# vu3.net
KiCad netlist of a schematic drawn in EAGLE
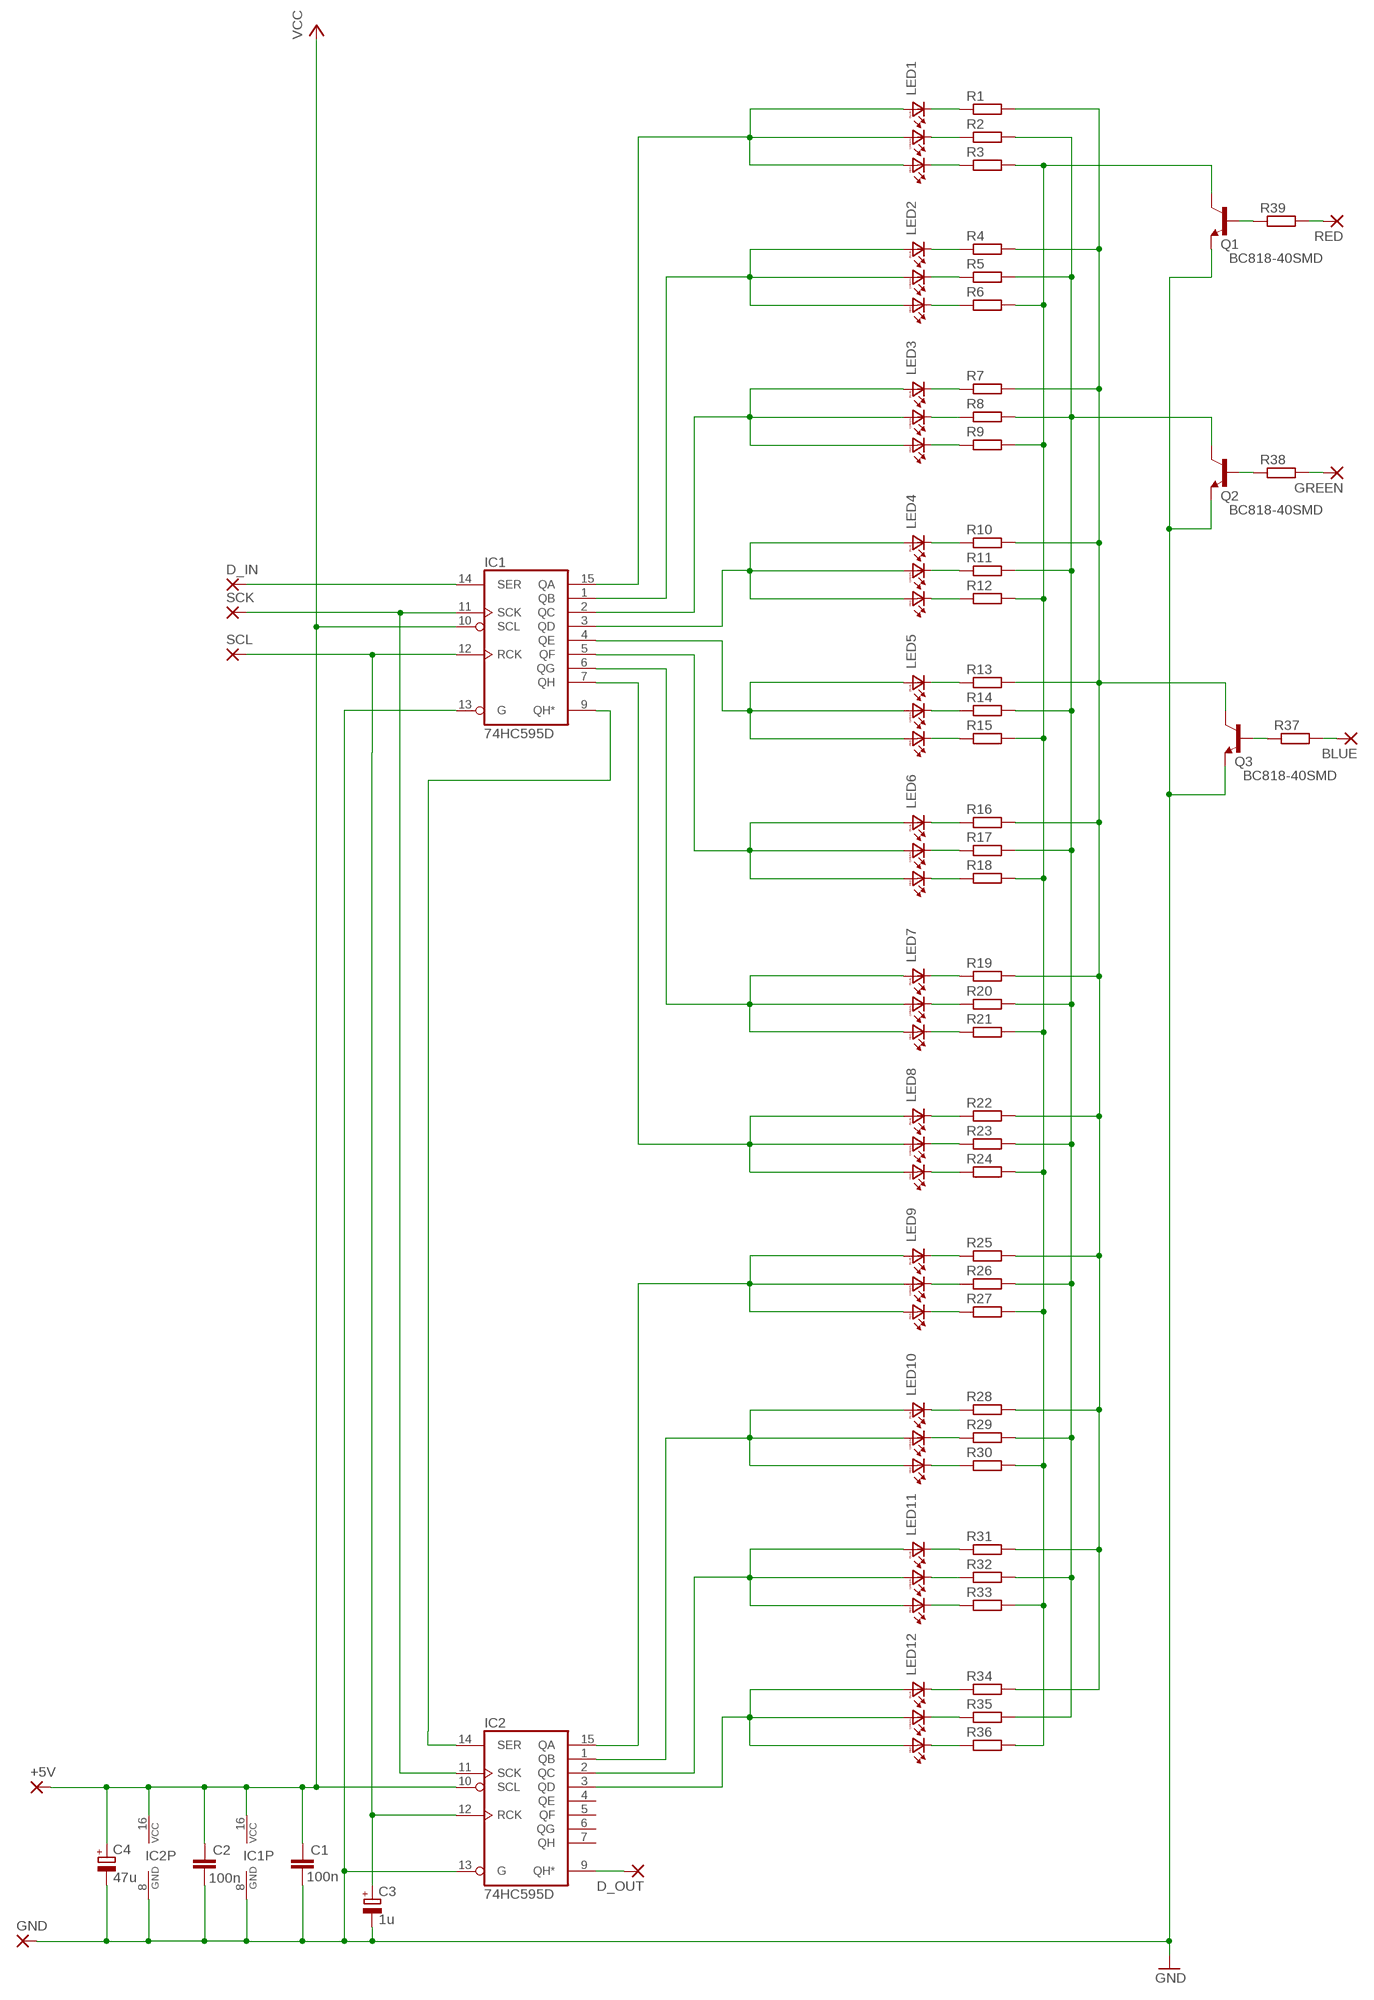
[diagram p0: schematic, sheet 1]

(export (version "E")
  (design (tool "Eeschema 10.0.6"))
  (components
    (comp (ref "+5V")
      (value "2,54/0,8")
      (footprint "eagle-import:2,54_0,8")
      (libsource (lib "eagle-import") (part "2,54/0,8"))
    )
    (comp (ref "BLUE")
      (value "2,54/0,8")
      (footprint "eagle-import:2,54_0,8")
      (libsource (lib "eagle-import") (part "2,54/0,8"))
    )
    (comp (ref "C1")
      (value "100n")
      (footprint "eagle-import:C1206")
      (libsource (lib "eagle-import") (part "C-EUC1206"))
    )
    (comp (ref "C2")
      (value "100n")
      (footprint "eagle-import:C1206")
      (libsource (lib "eagle-import") (part "C-EUC1206"))
    )
    (comp (ref "C3")
      (value "1u")
      (footprint "eagle-import:E5-5-L-12SMD")
      (libsource (lib "eagle-import") (part "CPOL-EUE5-5-L-12SMD"))
    )
    (comp (ref "C4")
      (value "47u")
      (footprint "eagle-import:E2,5-5-L-12SMD")
      (libsource (lib "eagle-import") (part "CPOL-EUE2.5-5-L-12-SMD"))
    )
    (comp (ref "D_IN")
      (value "2,54/0,8")
      (footprint "eagle-import:2,54_0,8")
      (libsource (lib "eagle-import") (part "2,54/0,8"))
    )
    (comp (ref "D_OUT")
      (value "2,54/0,8")
      (footprint "eagle-import:2,54_0,8")
      (libsource (lib "eagle-import") (part "2,54/0,8"))
    )
    (comp (ref "GND")
      (value "2,54/0,8")
      (footprint "eagle-import:2,54_0,8")
      (libsource (lib "eagle-import") (part "2,54/0,8"))
    )
    (comp (ref "GREEN")
      (value "2,54/0,8")
      (footprint "eagle-import:2,54_0,8")
      (libsource (lib "eagle-import") (part "2,54/0,8"))
    )
    (comp (ref "IC1")
      (value "74HC595D")
      (footprint "eagle-import:SO16")
      (libsource (lib "eagle-import") (part "74595DHC"))
    )
    (comp (ref "IC2")
      (value "74HC595D")
      (footprint "eagle-import:SO16")
      (libsource (lib "eagle-import") (part "74595DHC"))
    )
    (comp (ref "LED1")
      (value "LED_RGB_PLCC6")
      (footprint "eagle-import:PLCC6")
      (libsource (lib "eagle-import") (part "LED_RGB_PLCC6"))
    )
    (comp (ref "LED2")
      (value "LED_RGB_PLCC6")
      (footprint "eagle-import:PLCC6")
      (libsource (lib "eagle-import") (part "LED_RGB_PLCC6"))
    )
    (comp (ref "LED3")
      (value "LED_RGB_PLCC6")
      (footprint "eagle-import:PLCC6")
      (libsource (lib "eagle-import") (part "LED_RGB_PLCC6"))
    )
    (comp (ref "LED4")
      (value "LED_RGB_PLCC6")
      (footprint "eagle-import:PLCC6")
      (libsource (lib "eagle-import") (part "LED_RGB_PLCC6"))
    )
    (comp (ref "LED5")
      (value "LED_RGB_PLCC6")
      (footprint "eagle-import:PLCC6")
      (libsource (lib "eagle-import") (part "LED_RGB_PLCC6"))
    )
    (comp (ref "LED6")
      (value "LED_RGB_PLCC6")
      (footprint "eagle-import:PLCC6")
      (libsource (lib "eagle-import") (part "LED_RGB_PLCC6"))
    )
    (comp (ref "LED7")
      (value "LED_RGB_PLCC6")
      (footprint "eagle-import:PLCC6")
      (libsource (lib "eagle-import") (part "LED_RGB_PLCC6"))
    )
    (comp (ref "LED8")
      (value "LED_RGB_PLCC6")
      (footprint "eagle-import:PLCC6")
      (libsource (lib "eagle-import") (part "LED_RGB_PLCC6"))
    )
    (comp (ref "LED9")
      (value "LED_RGB_PLCC6")
      (footprint "eagle-import:PLCC6")
      (libsource (lib "eagle-import") (part "LED_RGB_PLCC6"))
    )
    (comp (ref "LED10")
      (value "LED_RGB_PLCC6")
      (footprint "eagle-import:PLCC6")
      (libsource (lib "eagle-import") (part "LED_RGB_PLCC6"))
    )
    (comp (ref "LED11")
      (value "LED_RGB_PLCC6")
      (footprint "eagle-import:PLCC6")
      (libsource (lib "eagle-import") (part "LED_RGB_PLCC6"))
    )
    (comp (ref "LED12")
      (value "LED_RGB_PLCC6")
      (footprint "eagle-import:PLCC6")
      (libsource (lib "eagle-import") (part "LED_RGB_PLCC6"))
    )
    (comp (ref "Q1")
      (value "BC818-40SMD")
      (footprint "eagle-import:SOT23-BEC")
      (libsource (lib "eagle-import") (part "BC818SMD-40"))
    )
    (comp (ref "Q2")
      (value "BC818-40SMD")
      (footprint "eagle-import:SOT23-BEC")
      (libsource (lib "eagle-import") (part "BC818SMD-40"))
    )
    (comp (ref "Q3")
      (value "BC818-40SMD")
      (footprint "eagle-import:SOT23-BEC")
      (libsource (lib "eagle-import") (part "BC818SMD-40"))
    )
    (comp (ref "R1")
      (value "R-EU_R1206")
      (footprint "eagle-import:R1206")
      (libsource (lib "eagle-import") (part "R-EU_R1206"))
    )
    (comp (ref "R2")
      (value "R-EU_R1206")
      (footprint "eagle-import:R1206")
      (libsource (lib "eagle-import") (part "R-EU_R1206"))
    )
    (comp (ref "R3")
      (value "R-EU_R1206")
      (footprint "eagle-import:R1206")
      (libsource (lib "eagle-import") (part "R-EU_R1206"))
    )
    (comp (ref "R4")
      (value "R-EU_R1206")
      (footprint "eagle-import:R1206")
      (libsource (lib "eagle-import") (part "R-EU_R1206"))
    )
    (comp (ref "R5")
      (value "R-EU_R1206")
      (footprint "eagle-import:R1206")
      (libsource (lib "eagle-import") (part "R-EU_R1206"))
    )
    (comp (ref "R6")
      (value "R-EU_R1206")
      (footprint "eagle-import:R1206")
      (libsource (lib "eagle-import") (part "R-EU_R1206"))
    )
    (comp (ref "R7")
      (value "R-EU_R1206")
      (footprint "eagle-import:R1206")
      (libsource (lib "eagle-import") (part "R-EU_R1206"))
    )
    (comp (ref "R8")
      (value "R-EU_R1206")
      (footprint "eagle-import:R1206")
      (libsource (lib "eagle-import") (part "R-EU_R1206"))
    )
    (comp (ref "R9")
      (value "R-EU_R1206")
      (footprint "eagle-import:R1206")
      (libsource (lib "eagle-import") (part "R-EU_R1206"))
    )
    (comp (ref "R10")
      (value "R-EU_R1206")
      (footprint "eagle-import:R1206")
      (libsource (lib "eagle-import") (part "R-EU_R1206"))
    )
    (comp (ref "R11")
      (value "R-EU_R1206")
      (footprint "eagle-import:R1206")
      (libsource (lib "eagle-import") (part "R-EU_R1206"))
    )
    (comp (ref "R12")
      (value "R-EU_R1206")
      (footprint "eagle-import:R1206")
      (libsource (lib "eagle-import") (part "R-EU_R1206"))
    )
    (comp (ref "R13")
      (value "R-EU_R1206")
      (footprint "eagle-import:R1206")
      (libsource (lib "eagle-import") (part "R-EU_R1206"))
    )
    (comp (ref "R14")
      (value "R-EU_R1206")
      (footprint "eagle-import:R1206")
      (libsource (lib "eagle-import") (part "R-EU_R1206"))
    )
    (comp (ref "R15")
      (value "R-EU_R1206")
      (footprint "eagle-import:R1206")
      (libsource (lib "eagle-import") (part "R-EU_R1206"))
    )
    (comp (ref "R16")
      (value "R-EU_R1206")
      (footprint "eagle-import:R1206")
      (libsource (lib "eagle-import") (part "R-EU_R1206"))
    )
    (comp (ref "R17")
      (value "R-EU_R1206")
      (footprint "eagle-import:R1206")
      (libsource (lib "eagle-import") (part "R-EU_R1206"))
    )
    (comp (ref "R18")
      (value "R-EU_R1206")
      (footprint "eagle-import:R1206")
      (libsource (lib "eagle-import") (part "R-EU_R1206"))
    )
    (comp (ref "R19")
      (value "R-EU_R1206")
      (footprint "eagle-import:R1206")
      (libsource (lib "eagle-import") (part "R-EU_R1206"))
    )
    (comp (ref "R20")
      (value "R-EU_R1206")
      (footprint "eagle-import:R1206")
      (libsource (lib "eagle-import") (part "R-EU_R1206"))
    )
    (comp (ref "R21")
      (value "R-EU_R1206")
      (footprint "eagle-import:R1206")
      (libsource (lib "eagle-import") (part "R-EU_R1206"))
    )
    (comp (ref "R22")
      (value "R-EU_R1206")
      (footprint "eagle-import:R1206")
      (libsource (lib "eagle-import") (part "R-EU_R1206"))
    )
    (comp (ref "R23")
      (value "R-EU_R1206")
      (footprint "eagle-import:R1206")
      (libsource (lib "eagle-import") (part "R-EU_R1206"))
    )
    (comp (ref "R24")
      (value "R-EU_R1206")
      (footprint "eagle-import:R1206")
      (libsource (lib "eagle-import") (part "R-EU_R1206"))
    )
    (comp (ref "R25")
      (value "R-EU_R1206")
      (footprint "eagle-import:R1206")
      (libsource (lib "eagle-import") (part "R-EU_R1206"))
    )
    (comp (ref "R26")
      (value "R-EU_R1206")
      (footprint "eagle-import:R1206")
      (libsource (lib "eagle-import") (part "R-EU_R1206"))
    )
    (comp (ref "R27")
      (value "R-EU_R1206")
      (footprint "eagle-import:R1206")
      (libsource (lib "eagle-import") (part "R-EU_R1206"))
    )
    (comp (ref "R28")
      (value "R-EU_R1206")
      (footprint "eagle-import:R1206")
      (libsource (lib "eagle-import") (part "R-EU_R1206"))
    )
    (comp (ref "R29")
      (value "R-EU_R1206")
      (footprint "eagle-import:R1206")
      (libsource (lib "eagle-import") (part "R-EU_R1206"))
    )
    (comp (ref "R30")
      (value "R-EU_R1206")
      (footprint "eagle-import:R1206")
      (libsource (lib "eagle-import") (part "R-EU_R1206"))
    )
    (comp (ref "R31")
      (value "R-EU_R1206")
      (footprint "eagle-import:R1206")
      (libsource (lib "eagle-import") (part "R-EU_R1206"))
    )
    (comp (ref "R32")
      (value "R-EU_R1206")
      (footprint "eagle-import:R1206")
      (libsource (lib "eagle-import") (part "R-EU_R1206"))
    )
    (comp (ref "R33")
      (value "R-EU_R1206")
      (footprint "eagle-import:R1206")
      (libsource (lib "eagle-import") (part "R-EU_R1206"))
    )
    (comp (ref "R34")
      (value "R-EU_R1206")
      (footprint "eagle-import:R1206")
      (libsource (lib "eagle-import") (part "R-EU_R1206"))
    )
    (comp (ref "R35")
      (value "R-EU_R1206")
      (footprint "eagle-import:R1206")
      (libsource (lib "eagle-import") (part "R-EU_R1206"))
    )
    (comp (ref "R36")
      (value "R-EU_R1206")
      (footprint "eagle-import:R1206")
      (libsource (lib "eagle-import") (part "R-EU_R1206"))
    )
    (comp (ref "R37")
      (value "R-EU_R1206")
      (footprint "eagle-import:R1206")
      (libsource (lib "eagle-import") (part "R-EU_R1206"))
    )
    (comp (ref "R38")
      (value "R-EU_R1206")
      (footprint "eagle-import:R1206")
      (libsource (lib "eagle-import") (part "R-EU_R1206"))
    )
    (comp (ref "R39")
      (value "R-EU_R1206")
      (footprint "eagle-import:R1206")
      (libsource (lib "eagle-import") (part "R-EU_R1206"))
    )
    (comp (ref "RED")
      (value "2,54/0,8")
      (footprint "eagle-import:2,54_0,8")
      (libsource (lib "eagle-import") (part "2,54/0,8"))
    )
    (comp (ref "SCK")
      (value "2,54/0,8")
      (footprint "eagle-import:2,54_0,8")
      (libsource (lib "eagle-import") (part "2,54/0,8"))
    )
    (comp (ref "SCL")
      (value "2,54/0,8")
      (footprint "eagle-import:2,54_0,8")
      (libsource (lib "eagle-import") (part "2,54/0,8"))
    )
  )
  (nets
    (net (code "1") (name "GND") (class "Default")
      (node (ref "C1") (pin "2") (pinfunction "2_2") (pintype "passive"))
      (node (ref "C2") (pin "2") (pinfunction "2_2") (pintype "passive"))
      (node (ref "C3") (pin "-") (pinfunction "-_-") (pintype "passive"))
      (node (ref "C4") (pin "-") (pinfunction "-_-") (pintype "passive"))
      (node (ref "GND") (pin "1") (pinfunction "P_1") (pintype "passive"))
      (node (ref "IC1") (pin "13") (pinfunction "G_13") (pintype "input"))
      (node (ref "IC1") (pin "8") (pinfunction "GND_8") (pintype "power_in"))
      (node (ref "IC2") (pin "13") (pinfunction "G_13") (pintype "input"))
      (node (ref "IC2") (pin "8") (pinfunction "GND_8") (pintype "power_in"))
      (node (ref "Q1") (pin "E") (pinfunction "E_E") (pintype "passive"))
      (node (ref "Q2") (pin "E") (pinfunction "E_E") (pintype "passive"))
      (node (ref "Q3") (pin "E") (pinfunction "E_E") (pintype "passive"))
    )
    (net (code "2") (name "Net-(BLUE-P)") (class "Default")
      (node (ref "BLUE") (pin "1") (pinfunction "P_1") (pintype "passive"))
      (node (ref "R37") (pin "2") (pinfunction "2_2") (pintype "passive"))
    )
    (net (code "3") (name "Net-(D_IN-P)") (class "Default")
      (node (ref "D_IN") (pin "1") (pinfunction "P_1") (pintype "passive"))
      (node (ref "IC1") (pin "14") (pinfunction "SER_14") (pintype "input"))
    )
    (net (code "4") (name "Net-(D_OUT-P)") (class "Default")
      (node (ref "D_OUT") (pin "1") (pinfunction "P_1") (pintype "passive"))
      (node (ref "IC2") (pin "9") (pinfunction "QH*_9") (pintype "tri_state"))
    )
    (net (code "5") (name "Net-(GREEN-P)") (class "Default")
      (node (ref "GREEN") (pin "1") (pinfunction "P_1") (pintype "passive"))
      (node (ref "R38") (pin "2") (pinfunction "2_2") (pintype "passive"))
    )
    (net (code "6") (name "Net-(IC1A-QA)") (class "Default")
      (node (ref "IC1") (pin "15") (pinfunction "QA_15") (pintype "tri_state"))
      (node (ref "LED1") (pin "BA") (pinfunction "BA_BA") (pintype "passive"))
      (node (ref "LED1") (pin "GA") (pinfunction "GA_GA") (pintype "passive"))
      (node (ref "LED1") (pin "RA") (pinfunction "RA_RA") (pintype "passive"))
    )
    (net (code "7") (name "Net-(IC1A-QB)") (class "Default")
      (node (ref "IC1") (pin "1") (pinfunction "QB_1") (pintype "tri_state"))
      (node (ref "LED2") (pin "BA") (pinfunction "BA_BA") (pintype "passive"))
      (node (ref "LED2") (pin "GA") (pinfunction "GA_GA") (pintype "passive"))
      (node (ref "LED2") (pin "RA") (pinfunction "RA_RA") (pintype "passive"))
    )
    (net (code "8") (name "Net-(IC1A-QC)") (class "Default")
      (node (ref "IC1") (pin "2") (pinfunction "QC_2") (pintype "tri_state"))
      (node (ref "LED3") (pin "BA") (pinfunction "BA_BA") (pintype "passive"))
      (node (ref "LED3") (pin "GA") (pinfunction "GA_GA") (pintype "passive"))
      (node (ref "LED3") (pin "RA") (pinfunction "RA_RA") (pintype "passive"))
    )
    (net (code "9") (name "Net-(IC1A-QD)") (class "Default")
      (node (ref "IC1") (pin "3") (pinfunction "QD_3") (pintype "tri_state"))
      (node (ref "LED4") (pin "BA") (pinfunction "BA_BA") (pintype "passive"))
      (node (ref "LED4") (pin "GA") (pinfunction "GA_GA") (pintype "passive"))
      (node (ref "LED4") (pin "RA") (pinfunction "RA_RA") (pintype "passive"))
    )
    (net (code "10") (name "Net-(IC1A-QE)") (class "Default")
      (node (ref "IC1") (pin "4") (pinfunction "QE_4") (pintype "tri_state"))
      (node (ref "LED5") (pin "BA") (pinfunction "BA_BA") (pintype "passive"))
      (node (ref "LED5") (pin "GA") (pinfunction "GA_GA") (pintype "passive"))
      (node (ref "LED5") (pin "RA") (pinfunction "RA_RA") (pintype "passive"))
    )
    (net (code "11") (name "Net-(IC1A-QF)") (class "Default")
      (node (ref "IC1") (pin "5") (pinfunction "QF_5") (pintype "tri_state"))
      (node (ref "LED6") (pin "BA") (pinfunction "BA_BA") (pintype "passive"))
      (node (ref "LED6") (pin "GA") (pinfunction "GA_GA") (pintype "passive"))
      (node (ref "LED6") (pin "RA") (pinfunction "RA_RA") (pintype "passive"))
    )
    (net (code "12") (name "Net-(IC1A-QG)") (class "Default")
      (node (ref "IC1") (pin "6") (pinfunction "QG_6") (pintype "tri_state"))
      (node (ref "LED7") (pin "BA") (pinfunction "BA_BA") (pintype "passive"))
      (node (ref "LED7") (pin "GA") (pinfunction "GA_GA") (pintype "passive"))
      (node (ref "LED7") (pin "RA") (pinfunction "RA_RA") (pintype "passive"))
    )
    (net (code "13") (name "Net-(IC1A-QH)") (class "Default")
      (node (ref "IC1") (pin "7") (pinfunction "QH_7") (pintype "tri_state"))
      (node (ref "LED8") (pin "BA") (pinfunction "BA_BA") (pintype "passive"))
      (node (ref "LED8") (pin "GA") (pinfunction "GA_GA") (pintype "passive"))
      (node (ref "LED8") (pin "RA") (pinfunction "RA_RA") (pintype "passive"))
    )
    (net (code "14") (name "Net-(IC1A-QH*)") (class "Default")
      (node (ref "IC1") (pin "9") (pinfunction "QH*_9") (pintype "tri_state"))
      (node (ref "IC2") (pin "14") (pinfunction "SER_14") (pintype "input"))
    )
    (net (code "15") (name "Net-(IC1A-RCK)") (class "Default")
      (node (ref "C3") (pin "+") (pinfunction "+_+") (pintype "passive"))
      (node (ref "IC1") (pin "12") (pinfunction "RCK_12") (pintype "input"))
      (node (ref "IC2") (pin "12") (pinfunction "RCK_12") (pintype "input"))
      (node (ref "SCL") (pin "1") (pinfunction "P_1") (pintype "passive"))
    )
    (net (code "16") (name "Net-(IC1A-SCK)") (class "Default")
      (node (ref "IC1") (pin "11") (pinfunction "SCK_11") (pintype "input"))
      (node (ref "IC2") (pin "11") (pinfunction "SCK_11") (pintype "input"))
      (node (ref "SCK") (pin "1") (pinfunction "P_1") (pintype "passive"))
    )
    (net (code "17") (name "Net-(IC2A-QA)") (class "Default")
      (node (ref "IC2") (pin "15") (pinfunction "QA_15") (pintype "tri_state"))
      (node (ref "LED9") (pin "BA") (pinfunction "BA_BA") (pintype "passive"))
      (node (ref "LED9") (pin "GA") (pinfunction "GA_GA") (pintype "passive"))
      (node (ref "LED9") (pin "RA") (pinfunction "RA_RA") (pintype "passive"))
    )
    (net (code "18") (name "Net-(IC2A-QB)") (class "Default")
      (node (ref "IC2") (pin "1") (pinfunction "QB_1") (pintype "tri_state"))
      (node (ref "LED10") (pin "BA") (pinfunction "BA_BA") (pintype "passive"))
      (node (ref "LED10") (pin "GA") (pinfunction "GA_GA") (pintype "passive"))
      (node (ref "LED10") (pin "RA") (pinfunction "RA_RA") (pintype "passive"))
    )
    (net (code "19") (name "Net-(IC2A-QC)") (class "Default")
      (node (ref "IC2") (pin "2") (pinfunction "QC_2") (pintype "tri_state"))
      (node (ref "LED11") (pin "BA") (pinfunction "BA_BA") (pintype "passive"))
      (node (ref "LED11") (pin "GA") (pinfunction "GA_GA") (pintype "passive"))
      (node (ref "LED11") (pin "RA") (pinfunction "RA_RA") (pintype "passive"))
    )
    (net (code "20") (name "Net-(IC2A-QD)") (class "Default")
      (node (ref "IC2") (pin "3") (pinfunction "QD_3") (pintype "tri_state"))
      (node (ref "LED12") (pin "BA") (pinfunction "BA_BA") (pintype "passive"))
      (node (ref "LED12") (pin "GA") (pinfunction "GA_GA") (pintype "passive"))
      (node (ref "LED12") (pin "RA") (pinfunction "RA_RA") (pintype "passive"))
    )
    (net (code "21") (name "Net-(LED1-PadBC)") (class "Default")
      (node (ref "LED1") (pin "BC") (pinfunction "BC_BC") (pintype "passive"))
      (node (ref "R1") (pin "1") (pinfunction "1_1") (pintype "passive"))
    )
    (net (code "22") (name "Net-(LED1-PadGC)") (class "Default")
      (node (ref "LED1") (pin "GC") (pinfunction "GC_GC") (pintype "passive"))
      (node (ref "R2") (pin "1") (pinfunction "1_1") (pintype "passive"))
    )
    (net (code "23") (name "Net-(LED1-PadRC)") (class "Default")
      (node (ref "LED1") (pin "RC") (pinfunction "RC_RC") (pintype "passive"))
      (node (ref "R3") (pin "1") (pinfunction "1_1") (pintype "passive"))
    )
    (net (code "24") (name "Net-(LED2-PadBC)") (class "Default")
      (node (ref "LED2") (pin "BC") (pinfunction "BC_BC") (pintype "passive"))
      (node (ref "R4") (pin "1") (pinfunction "1_1") (pintype "passive"))
    )
    (net (code "25") (name "Net-(LED2-PadGC)") (class "Default")
      (node (ref "LED2") (pin "GC") (pinfunction "GC_GC") (pintype "passive"))
      (node (ref "R5") (pin "1") (pinfunction "1_1") (pintype "passive"))
    )
    (net (code "26") (name "Net-(LED2-PadRC)") (class "Default")
      (node (ref "LED2") (pin "RC") (pinfunction "RC_RC") (pintype "passive"))
      (node (ref "R6") (pin "1") (pinfunction "1_1") (pintype "passive"))
    )
    (net (code "27") (name "Net-(LED3-PadBC)") (class "Default")
      (node (ref "LED3") (pin "BC") (pinfunction "BC_BC") (pintype "passive"))
      (node (ref "R7") (pin "1") (pinfunction "1_1") (pintype "passive"))
    )
    (net (code "28") (name "Net-(LED3-PadGC)") (class "Default")
      (node (ref "LED3") (pin "GC") (pinfunction "GC_GC") (pintype "passive"))
      (node (ref "R8") (pin "1") (pinfunction "1_1") (pintype "passive"))
    )
    (net (code "29") (name "Net-(LED3-PadRC)") (class "Default")
      (node (ref "LED3") (pin "RC") (pinfunction "RC_RC") (pintype "passive"))
      (node (ref "R9") (pin "1") (pinfunction "1_1") (pintype "passive"))
    )
    (net (code "30") (name "Net-(LED4-PadBC)") (class "Default")
      (node (ref "LED4") (pin "BC") (pinfunction "BC_BC") (pintype "passive"))
      (node (ref "R10") (pin "1") (pinfunction "1_1") (pintype "passive"))
    )
    (net (code "31") (name "Net-(LED4-PadGC)") (class "Default")
      (node (ref "LED4") (pin "GC") (pinfunction "GC_GC") (pintype "passive"))
      (node (ref "R11") (pin "1") (pinfunction "1_1") (pintype "passive"))
    )
    (net (code "32") (name "Net-(LED4-PadRC)") (class "Default")
      (node (ref "LED4") (pin "RC") (pinfunction "RC_RC") (pintype "passive"))
      (node (ref "R12") (pin "1") (pinfunction "1_1") (pintype "passive"))
    )
    (net (code "33") (name "Net-(LED5-PadBC)") (class "Default")
      (node (ref "LED5") (pin "BC") (pinfunction "BC_BC") (pintype "passive"))
      (node (ref "R13") (pin "1") (pinfunction "1_1") (pintype "passive"))
    )
    (net (code "34") (name "Net-(LED5-PadGC)") (class "Default")
      (node (ref "LED5") (pin "GC") (pinfunction "GC_GC") (pintype "passive"))
      (node (ref "R14") (pin "1") (pinfunction "1_1") (pintype "passive"))
    )
    (net (code "35") (name "Net-(LED5-PadRC)") (class "Default")
      (node (ref "LED5") (pin "RC") (pinfunction "RC_RC") (pintype "passive"))
      (node (ref "R15") (pin "1") (pinfunction "1_1") (pintype "passive"))
    )
    (net (code "36") (name "Net-(LED6-PadBC)") (class "Default")
      (node (ref "LED6") (pin "BC") (pinfunction "BC_BC") (pintype "passive"))
      (node (ref "R16") (pin "1") (pinfunction "1_1") (pintype "passive"))
    )
    (net (code "37") (name "Net-(LED6-PadGC)") (class "Default")
      (node (ref "LED6") (pin "GC") (pinfunction "GC_GC") (pintype "passive"))
      (node (ref "R17") (pin "1") (pinfunction "1_1") (pintype "passive"))
    )
    (net (code "38") (name "Net-(LED6-PadRC)") (class "Default")
      (node (ref "LED6") (pin "RC") (pinfunction "RC_RC") (pintype "passive"))
      (node (ref "R18") (pin "1") (pinfunction "1_1") (pintype "passive"))
    )
    (net (code "39") (name "Net-(LED7-PadBC)") (class "Default")
      (node (ref "LED7") (pin "BC") (pinfunction "BC_BC") (pintype "passive"))
      (node (ref "R19") (pin "1") (pinfunction "1_1") (pintype "passive"))
    )
    (net (code "40") (name "Net-(LED7-PadGC)") (class "Default")
      (node (ref "LED7") (pin "GC") (pinfunction "GC_GC") (pintype "passive"))
      (node (ref "R20") (pin "1") (pinfunction "1_1") (pintype "passive"))
    )
    (net (code "41") (name "Net-(LED7-PadRC)") (class "Default")
      (node (ref "LED7") (pin "RC") (pinfunction "RC_RC") (pintype "passive"))
      (node (ref "R21") (pin "1") (pinfunction "1_1") (pintype "passive"))
    )
    (net (code "42") (name "Net-(LED8-PadBC)") (class "Default")
      (node (ref "LED8") (pin "BC") (pinfunction "BC_BC") (pintype "passive"))
      (node (ref "R22") (pin "1") (pinfunction "1_1") (pintype "passive"))
    )
    (net (code "43") (name "Net-(LED8-PadGC)") (class "Default")
      (node (ref "LED8") (pin "GC") (pinfunction "GC_GC") (pintype "passive"))
      (node (ref "R23") (pin "1") (pinfunction "1_1") (pintype "passive"))
    )
    (net (code "44") (name "Net-(LED8-PadRC)") (class "Default")
      (node (ref "LED8") (pin "RC") (pinfunction "RC_RC") (pintype "passive"))
      (node (ref "R24") (pin "1") (pinfunction "1_1") (pintype "passive"))
    )
    (net (code "45") (name "Net-(LED9-PadBC)") (class "Default")
      (node (ref "LED9") (pin "BC") (pinfunction "BC_BC") (pintype "passive"))
      (node (ref "R25") (pin "1") (pinfunction "1_1") (pintype "passive"))
    )
    (net (code "46") (name "Net-(LED9-PadGC)") (class "Default")
      (node (ref "LED9") (pin "GC") (pinfunction "GC_GC") (pintype "passive"))
      (node (ref "R26") (pin "1") (pinfunction "1_1") (pintype "passive"))
    )
    (net (code "47") (name "Net-(LED9-PadRC)") (class "Default")
      (node (ref "LED9") (pin "RC") (pinfunction "RC_RC") (pintype "passive"))
      (node (ref "R27") (pin "1") (pinfunction "1_1") (pintype "passive"))
    )
    (net (code "48") (name "Net-(LED10-PadBC)") (class "Default")
      (node (ref "LED10") (pin "BC") (pinfunction "BC_BC") (pintype "passive"))
      (node (ref "R28") (pin "1") (pinfunction "1_1") (pintype "passive"))
    )
    (net (code "49") (name "Net-(LED10-PadGC)") (class "Default")
      (node (ref "LED10") (pin "GC") (pinfunction "GC_GC") (pintype "passive"))
      (node (ref "R29") (pin "1") (pinfunction "1_1") (pintype "passive"))
    )
    (net (code "50") (name "Net-(LED10-PadRC)") (class "Default")
      (node (ref "LED10") (pin "RC") (pinfunction "RC_RC") (pintype "passive"))
      (node (ref "R30") (pin "1") (pinfunction "1_1") (pintype "passive"))
    )
    (net (code "51") (name "Net-(LED11-PadBC)") (class "Default")
      (node (ref "LED11") (pin "BC") (pinfunction "BC_BC") (pintype "passive"))
      (node (ref "R31") (pin "1") (pinfunction "1_1") (pintype "passive"))
    )
    (net (code "52") (name "Net-(LED11-PadGC)") (class "Default")
      (node (ref "LED11") (pin "GC") (pinfunction "GC_GC") (pintype "passive"))
      (node (ref "R32") (pin "1") (pinfunction "1_1") (pintype "passive"))
    )
    (net (code "53") (name "Net-(LED11-PadRC)") (class "Default")
      (node (ref "LED11") (pin "RC") (pinfunction "RC_RC") (pintype "passive"))
      (node (ref "R33") (pin "1") (pinfunction "1_1") (pintype "passive"))
    )
    (net (code "54") (name "Net-(LED12-PadBC)") (class "Default")
      (node (ref "LED12") (pin "BC") (pinfunction "BC_BC") (pintype "passive"))
      (node (ref "R34") (pin "1") (pinfunction "1_1") (pintype "passive"))
    )
    (net (code "55") (name "Net-(LED12-PadGC)") (class "Default")
      (node (ref "LED12") (pin "GC") (pinfunction "GC_GC") (pintype "passive"))
      (node (ref "R35") (pin "1") (pinfunction "1_1") (pintype "passive"))
    )
    (net (code "56") (name "Net-(LED12-PadRC)") (class "Default")
      (node (ref "LED12") (pin "RC") (pinfunction "RC_RC") (pintype "passive"))
      (node (ref "R36") (pin "1") (pinfunction "1_1") (pintype "passive"))
    )
    (net (code "57") (name "Net-(Q1-PadB)") (class "Default")
      (node (ref "Q1") (pin "B") (pinfunction "B_B") (pintype "passive"))
      (node (ref "R39") (pin "1") (pinfunction "1_1") (pintype "passive"))
    )
    (net (code "58") (name "Net-(Q1-PadC)") (class "Default")
      (node (ref "Q1") (pin "C") (pinfunction "C_C") (pintype "passive"))
      (node (ref "R12") (pin "2") (pinfunction "2_2") (pintype "passive"))
      (node (ref "R15") (pin "2") (pinfunction "2_2") (pintype "passive"))
      (node (ref "R18") (pin "2") (pinfunction "2_2") (pintype "passive"))
      (node (ref "R21") (pin "2") (pinfunction "2_2") (pintype "passive"))
      (node (ref "R24") (pin "2") (pinfunction "2_2") (pintype "passive"))
      (node (ref "R27") (pin "2") (pinfunction "2_2") (pintype "passive"))
      (node (ref "R3") (pin "2") (pinfunction "2_2") (pintype "passive"))
      (node (ref "R30") (pin "2") (pinfunction "2_2") (pintype "passive"))
      (node (ref "R33") (pin "2") (pinfunction "2_2") (pintype "passive"))
      (node (ref "R36") (pin "2") (pinfunction "2_2") (pintype "passive"))
      (node (ref "R6") (pin "2") (pinfunction "2_2") (pintype "passive"))
      (node (ref "R9") (pin "2") (pinfunction "2_2") (pintype "passive"))
    )
    (net (code "59") (name "Net-(Q2-PadB)") (class "Default")
      (node (ref "Q2") (pin "B") (pinfunction "B_B") (pintype "passive"))
      (node (ref "R38") (pin "1") (pinfunction "1_1") (pintype "passive"))
    )
    (net (code "60") (name "Net-(Q2-PadC)") (class "Default")
      (node (ref "Q2") (pin "C") (pinfunction "C_C") (pintype "passive"))
      (node (ref "R11") (pin "2") (pinfunction "2_2") (pintype "passive"))
      (node (ref "R14") (pin "2") (pinfunction "2_2") (pintype "passive"))
      (node (ref "R17") (pin "2") (pinfunction "2_2") (pintype "passive"))
      (node (ref "R2") (pin "2") (pinfunction "2_2") (pintype "passive"))
      (node (ref "R20") (pin "2") (pinfunction "2_2") (pintype "passive"))
      (node (ref "R23") (pin "2") (pinfunction "2_2") (pintype "passive"))
      (node (ref "R26") (pin "2") (pinfunction "2_2") (pintype "passive"))
      (node (ref "R29") (pin "2") (pinfunction "2_2") (pintype "passive"))
      (node (ref "R32") (pin "2") (pinfunction "2_2") (pintype "passive"))
      (node (ref "R35") (pin "2") (pinfunction "2_2") (pintype "passive"))
      (node (ref "R5") (pin "2") (pinfunction "2_2") (pintype "passive"))
      (node (ref "R8") (pin "2") (pinfunction "2_2") (pintype "passive"))
    )
    (net (code "61") (name "Net-(Q3-PadB)") (class "Default")
      (node (ref "Q3") (pin "B") (pinfunction "B_B") (pintype "passive"))
      (node (ref "R37") (pin "1") (pinfunction "1_1") (pintype "passive"))
    )
    (net (code "62") (name "Net-(Q3-PadC)") (class "Default")
      (node (ref "Q3") (pin "C") (pinfunction "C_C") (pintype "passive"))
      (node (ref "R1") (pin "2") (pinfunction "2_2") (pintype "passive"))
      (node (ref "R10") (pin "2") (pinfunction "2_2") (pintype "passive"))
      (node (ref "R13") (pin "2") (pinfunction "2_2") (pintype "passive"))
      (node (ref "R16") (pin "2") (pinfunction "2_2") (pintype "passive"))
      (node (ref "R19") (pin "2") (pinfunction "2_2") (pintype "passive"))
      (node (ref "R22") (pin "2") (pinfunction "2_2") (pintype "passive"))
      (node (ref "R25") (pin "2") (pinfunction "2_2") (pintype "passive"))
      (node (ref "R28") (pin "2") (pinfunction "2_2") (pintype "passive"))
      (node (ref "R31") (pin "2") (pinfunction "2_2") (pintype "passive"))
      (node (ref "R34") (pin "2") (pinfunction "2_2") (pintype "passive"))
      (node (ref "R4") (pin "2") (pinfunction "2_2") (pintype "passive"))
      (node (ref "R7") (pin "2") (pinfunction "2_2") (pintype "passive"))
    )
    (net (code "63") (name "Net-(RED-P)") (class "Default")
      (node (ref "R39") (pin "2") (pinfunction "2_2") (pintype "passive"))
      (node (ref "RED") (pin "1") (pinfunction "P_1") (pintype "passive"))
    )
    (net (code "64") (name "VCC") (class "Default")
      (node (ref "+5V") (pin "1") (pinfunction "P_1") (pintype "passive"))
      (node (ref "C1") (pin "1") (pinfunction "1_1") (pintype "passive"))
      (node (ref "C2") (pin "1") (pinfunction "1_1") (pintype "passive"))
      (node (ref "C4") (pin "+") (pinfunction "+_+") (pintype "passive"))
      (node (ref "IC1") (pin "10") (pinfunction "SCL_10") (pintype "input"))
      (node (ref "IC1") (pin "16") (pinfunction "VCC_16") (pintype "power_in"))
      (node (ref "IC2") (pin "10") (pinfunction "SCL_10") (pintype "input"))
      (node (ref "IC2") (pin "16") (pinfunction "VCC_16") (pintype "power_in"))
    )
    (net (code "65") (name "unconnected-(IC2A-QE-Pad4)") (class "Default")
      (node (ref "IC2") (pin "4") (pinfunction "QE_4") (pintype "tri_state"))
    )
    (net (code "66") (name "unconnected-(IC2A-QF-Pad5)") (class "Default")
      (node (ref "IC2") (pin "5") (pinfunction "QF_5") (pintype "tri_state"))
    )
    (net (code "67") (name "unconnected-(IC2A-QG-Pad6)") (class "Default")
      (node (ref "IC2") (pin "6") (pinfunction "QG_6") (pintype "tri_state"))
    )
    (net (code "68") (name "unconnected-(IC2A-QH-Pad7)") (class "Default")
      (node (ref "IC2") (pin "7") (pinfunction "QH_7") (pintype "tri_state"))
    )
  )
)
